# 2ND_SCHEMATIC.net
KiCad netlist of a schematic drawn in EAGLE
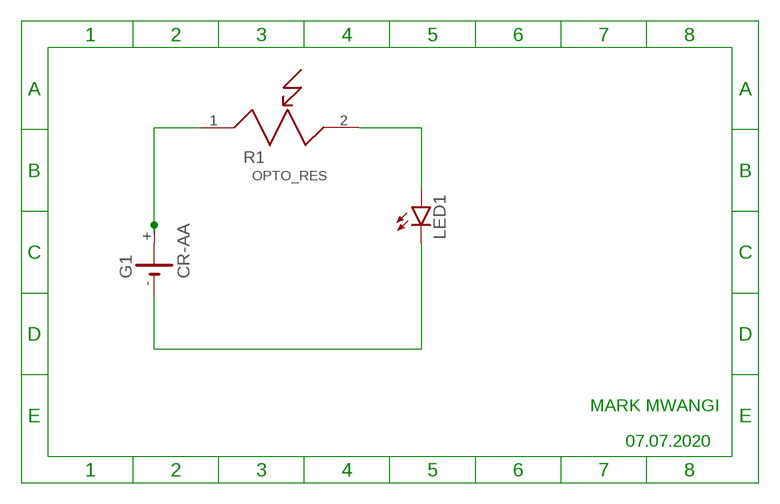
[diagram p0: schematic, sheet 1]

(export (version "E")
  (design (tool "Eeschema 10.0.6"))
  (components
    (comp (ref "G1")
      (value "CR-AA")
      (footprint "eagle-import:CRAA")
      (libsource (lib "eagle-import") (part "CR-AA"))
    )
    (comp (ref "LED1")
      (value "LED5MM")
      (footprint "eagle-import:LED5MM")
      (libsource (lib "eagle-import") (part "LED5MM"))
    )
    (comp (ref "R1")
      (value "OPTO_RES")
      (footprint "eagle-import:OPTO_RES")
      (libsource (lib "eagle-import") (part "OPTO_RES"))
    )
  )
  (nets
    (net (code "1") (name "Net-(LED1-C)") (class "Default")
      (node (ref "G1") (pin "-") (pinfunction "-_-") (pintype "passive"))
      (node (ref "LED1") (pin "K") (pinfunction "C_K") (pintype "passive"))
    )
    (net (code "2") (name "Net-(R1-P1)") (class "Default")
      (node (ref "G1") (pin "+") (pinfunction "+_+") (pintype "passive"))
      (node (ref "R1") (pin "1") (pinfunction "P1_1") (pintype "bidirectional"))
    )
    (net (code "3") (name "Net-(R1-P2)") (class "Default")
      (node (ref "LED1") (pin "A") (pinfunction "A_A") (pintype "passive"))
      (node (ref "R1") (pin "2") (pinfunction "P2_2") (pintype "bidirectional"))
    )
    (net (code "4") (name "unconnected-(G1-+-Pad+@1)") (class "Default")
      (node (ref "G1") (pin "+@1") (pinfunction "+_+@1") (pintype "passive"))
    )
  )
)
